# RW_CAN_v2.net
KiCad netlist of a schematic drawn in EAGLE
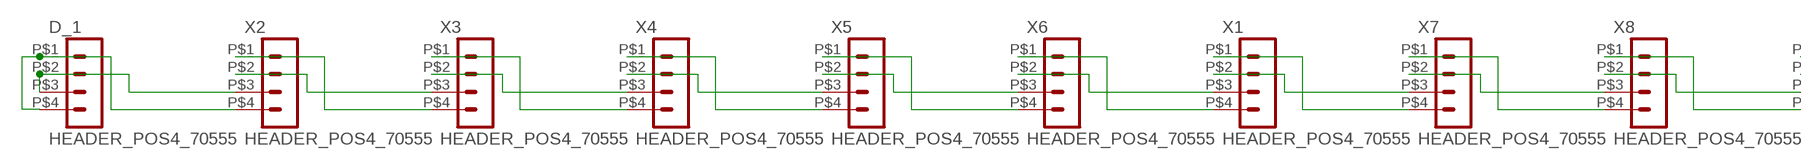
[diagram p0: schematic, sheet 1, part 1 of 2]
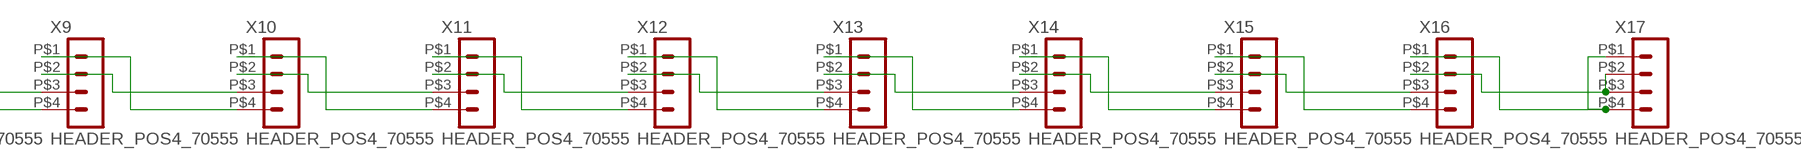
[diagram p1: schematic, sheet 1, part 2 of 2]

(export (version "E")
  (design (tool "Eeschema 10.0.6"))
  (components
    (comp (ref "D_1")
      (value "HEADER_POS4_70555")
      (footprint "eagle-import:70555-POS4")
      (libsource (lib "eagle-import") (part "HEADER_POS4_?70555"))
    )
    (comp (ref "X1")
      (value "HEADER_POS4_70555")
      (footprint "eagle-import:70555-POS4")
      (libsource (lib "eagle-import") (part "HEADER_POS4_?70555"))
    )
    (comp (ref "X2")
      (value "HEADER_POS4_70555")
      (footprint "eagle-import:70555-POS4")
      (libsource (lib "eagle-import") (part "HEADER_POS4_?70555"))
    )
    (comp (ref "X3")
      (value "HEADER_POS4_70555")
      (footprint "eagle-import:70555-POS4")
      (libsource (lib "eagle-import") (part "HEADER_POS4_?70555"))
    )
    (comp (ref "X4")
      (value "HEADER_POS4_70555")
      (footprint "eagle-import:70555-POS4")
      (libsource (lib "eagle-import") (part "HEADER_POS4_?70555"))
    )
    (comp (ref "X5")
      (value "HEADER_POS4_70555")
      (footprint "eagle-import:70555-POS4")
      (libsource (lib "eagle-import") (part "HEADER_POS4_?70555"))
    )
    (comp (ref "X6")
      (value "HEADER_POS4_70555")
      (footprint "eagle-import:70555-POS4")
      (libsource (lib "eagle-import") (part "HEADER_POS4_?70555"))
    )
    (comp (ref "X7")
      (value "HEADER_POS4_70555")
      (footprint "eagle-import:70555-POS4")
      (libsource (lib "eagle-import") (part "HEADER_POS4_?70555"))
    )
    (comp (ref "X8")
      (value "HEADER_POS4_70555")
      (footprint "eagle-import:70555-POS4")
      (libsource (lib "eagle-import") (part "HEADER_POS4_?70555"))
    )
    (comp (ref "X9")
      (value "HEADER_POS4_70555")
      (footprint "eagle-import:70555-POS4")
      (libsource (lib "eagle-import") (part "HEADER_POS4_?70555"))
    )
    (comp (ref "X10")
      (value "HEADER_POS4_70555")
      (footprint "eagle-import:70555-POS4")
      (libsource (lib "eagle-import") (part "HEADER_POS4_?70555"))
    )
    (comp (ref "X11")
      (value "HEADER_POS4_70555")
      (footprint "eagle-import:70555-POS4")
      (libsource (lib "eagle-import") (part "HEADER_POS4_?70555"))
    )
    (comp (ref "X12")
      (value "HEADER_POS4_70555")
      (footprint "eagle-import:70555-POS4")
      (libsource (lib "eagle-import") (part "HEADER_POS4_?70555"))
    )
    (comp (ref "X13")
      (value "HEADER_POS4_70555")
      (footprint "eagle-import:70555-POS4")
      (libsource (lib "eagle-import") (part "HEADER_POS4_?70555"))
    )
    (comp (ref "X14")
      (value "HEADER_POS4_70555")
      (footprint "eagle-import:70555-POS4")
      (libsource (lib "eagle-import") (part "HEADER_POS4_?70555"))
    )
    (comp (ref "X15")
      (value "HEADER_POS4_70555")
      (footprint "eagle-import:70555-POS4")
      (libsource (lib "eagle-import") (part "HEADER_POS4_?70555"))
    )
    (comp (ref "X16")
      (value "HEADER_POS4_70555")
      (footprint "eagle-import:70555-POS4")
      (libsource (lib "eagle-import") (part "HEADER_POS4_?70555"))
    )
    (comp (ref "X17")
      (value "HEADER_POS4_70555")
      (footprint "eagle-import:70555-POS4")
      (libsource (lib "eagle-import") (part "HEADER_POS4_?70555"))
    )
  )
  (nets
    (net (code "1") (name "Net-(D_1-1)") (class "Default")
      (node (ref "D_1") (pin "P$1") (pinfunction "1_P$1") (pintype "passive"))
      (node (ref "D_1") (pin "P$4") (pinfunction "4_P$4") (pintype "passive"))
      (node (ref "X2") (pin "P$4") (pinfunction "4_P$4") (pintype "passive"))
    )
    (net (code "2") (name "Net-(D_1-2)") (class "Default")
      (node (ref "D_1") (pin "P$2") (pinfunction "2_P$2") (pintype "passive"))
      (node (ref "D_1") (pin "P$3") (pinfunction "3_P$3") (pintype "passive"))
      (node (ref "X2") (pin "P$3") (pinfunction "3_P$3") (pintype "passive"))
    )
    (net (code "3") (name "Net-(X1-1)") (class "Default")
      (node (ref "X1") (pin "P$1") (pinfunction "1_P$1") (pintype "passive"))
      (node (ref "X7") (pin "P$4") (pinfunction "4_P$4") (pintype "passive"))
    )
    (net (code "4") (name "Net-(X1-2)") (class "Default")
      (node (ref "X1") (pin "P$2") (pinfunction "2_P$2") (pintype "passive"))
      (node (ref "X7") (pin "P$3") (pinfunction "3_P$3") (pintype "passive"))
    )
    (net (code "5") (name "Net-(X1-3)") (class "Default")
      (node (ref "X1") (pin "P$3") (pinfunction "3_P$3") (pintype "passive"))
      (node (ref "X6") (pin "P$2") (pinfunction "2_P$2") (pintype "passive"))
    )
    (net (code "6") (name "Net-(X1-4)") (class "Default")
      (node (ref "X1") (pin "P$4") (pinfunction "4_P$4") (pintype "passive"))
      (node (ref "X6") (pin "P$1") (pinfunction "1_P$1") (pintype "passive"))
    )
    (net (code "7") (name "Net-(X2-1)") (class "Default")
      (node (ref "X2") (pin "P$1") (pinfunction "1_P$1") (pintype "passive"))
      (node (ref "X3") (pin "P$4") (pinfunction "4_P$4") (pintype "passive"))
    )
    (net (code "8") (name "Net-(X2-2)") (class "Default")
      (node (ref "X2") (pin "P$2") (pinfunction "2_P$2") (pintype "passive"))
      (node (ref "X3") (pin "P$3") (pinfunction "3_P$3") (pintype "passive"))
    )
    (net (code "9") (name "Net-(X3-1)") (class "Default")
      (node (ref "X3") (pin "P$1") (pinfunction "1_P$1") (pintype "passive"))
      (node (ref "X4") (pin "P$4") (pinfunction "4_P$4") (pintype "passive"))
    )
    (net (code "10") (name "Net-(X3-2)") (class "Default")
      (node (ref "X3") (pin "P$2") (pinfunction "2_P$2") (pintype "passive"))
      (node (ref "X4") (pin "P$3") (pinfunction "3_P$3") (pintype "passive"))
    )
    (net (code "11") (name "Net-(X4-1)") (class "Default")
      (node (ref "X4") (pin "P$1") (pinfunction "1_P$1") (pintype "passive"))
      (node (ref "X5") (pin "P$4") (pinfunction "4_P$4") (pintype "passive"))
    )
    (net (code "12") (name "Net-(X4-2)") (class "Default")
      (node (ref "X4") (pin "P$2") (pinfunction "2_P$2") (pintype "passive"))
      (node (ref "X5") (pin "P$3") (pinfunction "3_P$3") (pintype "passive"))
    )
    (net (code "13") (name "Net-(X5-1)") (class "Default")
      (node (ref "X5") (pin "P$1") (pinfunction "1_P$1") (pintype "passive"))
      (node (ref "X6") (pin "P$4") (pinfunction "4_P$4") (pintype "passive"))
    )
    (net (code "14") (name "Net-(X5-2)") (class "Default")
      (node (ref "X5") (pin "P$2") (pinfunction "2_P$2") (pintype "passive"))
      (node (ref "X6") (pin "P$3") (pinfunction "3_P$3") (pintype "passive"))
    )
    (net (code "15") (name "Net-(X7-1)") (class "Default")
      (node (ref "X7") (pin "P$1") (pinfunction "1_P$1") (pintype "passive"))
      (node (ref "X8") (pin "P$4") (pinfunction "4_P$4") (pintype "passive"))
    )
    (net (code "16") (name "Net-(X7-2)") (class "Default")
      (node (ref "X7") (pin "P$2") (pinfunction "2_P$2") (pintype "passive"))
      (node (ref "X8") (pin "P$3") (pinfunction "3_P$3") (pintype "passive"))
    )
    (net (code "17") (name "Net-(X8-1)") (class "Default")
      (node (ref "X8") (pin "P$1") (pinfunction "1_P$1") (pintype "passive"))
      (node (ref "X9") (pin "P$4") (pinfunction "4_P$4") (pintype "passive"))
    )
    (net (code "18") (name "Net-(X8-2)") (class "Default")
      (node (ref "X8") (pin "P$2") (pinfunction "2_P$2") (pintype "passive"))
      (node (ref "X9") (pin "P$3") (pinfunction "3_P$3") (pintype "passive"))
    )
    (net (code "19") (name "Net-(X10-1)") (class "Default")
      (node (ref "X10") (pin "P$1") (pinfunction "1_P$1") (pintype "passive"))
      (node (ref "X11") (pin "P$4") (pinfunction "4_P$4") (pintype "passive"))
    )
    (net (code "20") (name "Net-(X10-2)") (class "Default")
      (node (ref "X10") (pin "P$2") (pinfunction "2_P$2") (pintype "passive"))
      (node (ref "X11") (pin "P$3") (pinfunction "3_P$3") (pintype "passive"))
    )
    (net (code "21") (name "Net-(X10-3)") (class "Default")
      (node (ref "X10") (pin "P$3") (pinfunction "3_P$3") (pintype "passive"))
      (node (ref "X9") (pin "P$2") (pinfunction "2_P$2") (pintype "passive"))
    )
    (net (code "22") (name "Net-(X10-4)") (class "Default")
      (node (ref "X10") (pin "P$4") (pinfunction "4_P$4") (pintype "passive"))
      (node (ref "X9") (pin "P$1") (pinfunction "1_P$1") (pintype "passive"))
    )
    (net (code "23") (name "Net-(X11-1)") (class "Default")
      (node (ref "X11") (pin "P$1") (pinfunction "1_P$1") (pintype "passive"))
      (node (ref "X12") (pin "P$4") (pinfunction "4_P$4") (pintype "passive"))
    )
    (net (code "24") (name "Net-(X11-2)") (class "Default")
      (node (ref "X11") (pin "P$2") (pinfunction "2_P$2") (pintype "passive"))
      (node (ref "X12") (pin "P$3") (pinfunction "3_P$3") (pintype "passive"))
    )
    (net (code "25") (name "Net-(X12-1)") (class "Default")
      (node (ref "X12") (pin "P$1") (pinfunction "1_P$1") (pintype "passive"))
      (node (ref "X13") (pin "P$4") (pinfunction "4_P$4") (pintype "passive"))
    )
    (net (code "26") (name "Net-(X12-2)") (class "Default")
      (node (ref "X12") (pin "P$2") (pinfunction "2_P$2") (pintype "passive"))
      (node (ref "X13") (pin "P$3") (pinfunction "3_P$3") (pintype "passive"))
    )
    (net (code "27") (name "Net-(X13-1)") (class "Default")
      (node (ref "X13") (pin "P$1") (pinfunction "1_P$1") (pintype "passive"))
      (node (ref "X14") (pin "P$4") (pinfunction "4_P$4") (pintype "passive"))
    )
    (net (code "28") (name "Net-(X13-2)") (class "Default")
      (node (ref "X13") (pin "P$2") (pinfunction "2_P$2") (pintype "passive"))
      (node (ref "X14") (pin "P$3") (pinfunction "3_P$3") (pintype "passive"))
    )
    (net (code "29") (name "Net-(X14-1)") (class "Default")
      (node (ref "X14") (pin "P$1") (pinfunction "1_P$1") (pintype "passive"))
      (node (ref "X15") (pin "P$4") (pinfunction "4_P$4") (pintype "passive"))
    )
    (net (code "30") (name "Net-(X14-2)") (class "Default")
      (node (ref "X14") (pin "P$2") (pinfunction "2_P$2") (pintype "passive"))
      (node (ref "X15") (pin "P$3") (pinfunction "3_P$3") (pintype "passive"))
    )
    (net (code "31") (name "Net-(X15-1)") (class "Default")
      (node (ref "X15") (pin "P$1") (pinfunction "1_P$1") (pintype "passive"))
      (node (ref "X16") (pin "P$4") (pinfunction "4_P$4") (pintype "passive"))
    )
    (net (code "32") (name "Net-(X15-2)") (class "Default")
      (node (ref "X15") (pin "P$2") (pinfunction "2_P$2") (pintype "passive"))
      (node (ref "X16") (pin "P$3") (pinfunction "3_P$3") (pintype "passive"))
    )
    (net (code "33") (name "Net-(X16-1)") (class "Default")
      (node (ref "X16") (pin "P$1") (pinfunction "1_P$1") (pintype "passive"))
      (node (ref "X17") (pin "P$1") (pinfunction "1_P$1") (pintype "passive"))
      (node (ref "X17") (pin "P$4") (pinfunction "4_P$4") (pintype "passive"))
    )
    (net (code "34") (name "Net-(X16-2)") (class "Default")
      (node (ref "X16") (pin "P$2") (pinfunction "2_P$2") (pintype "passive"))
      (node (ref "X17") (pin "P$2") (pinfunction "2_P$2") (pintype "passive"))
      (node (ref "X17") (pin "P$3") (pinfunction "3_P$3") (pintype "passive"))
    )
  )
)
